# controlador_valvulas.net
KiCad netlist of a schematic drawn in EAGLE
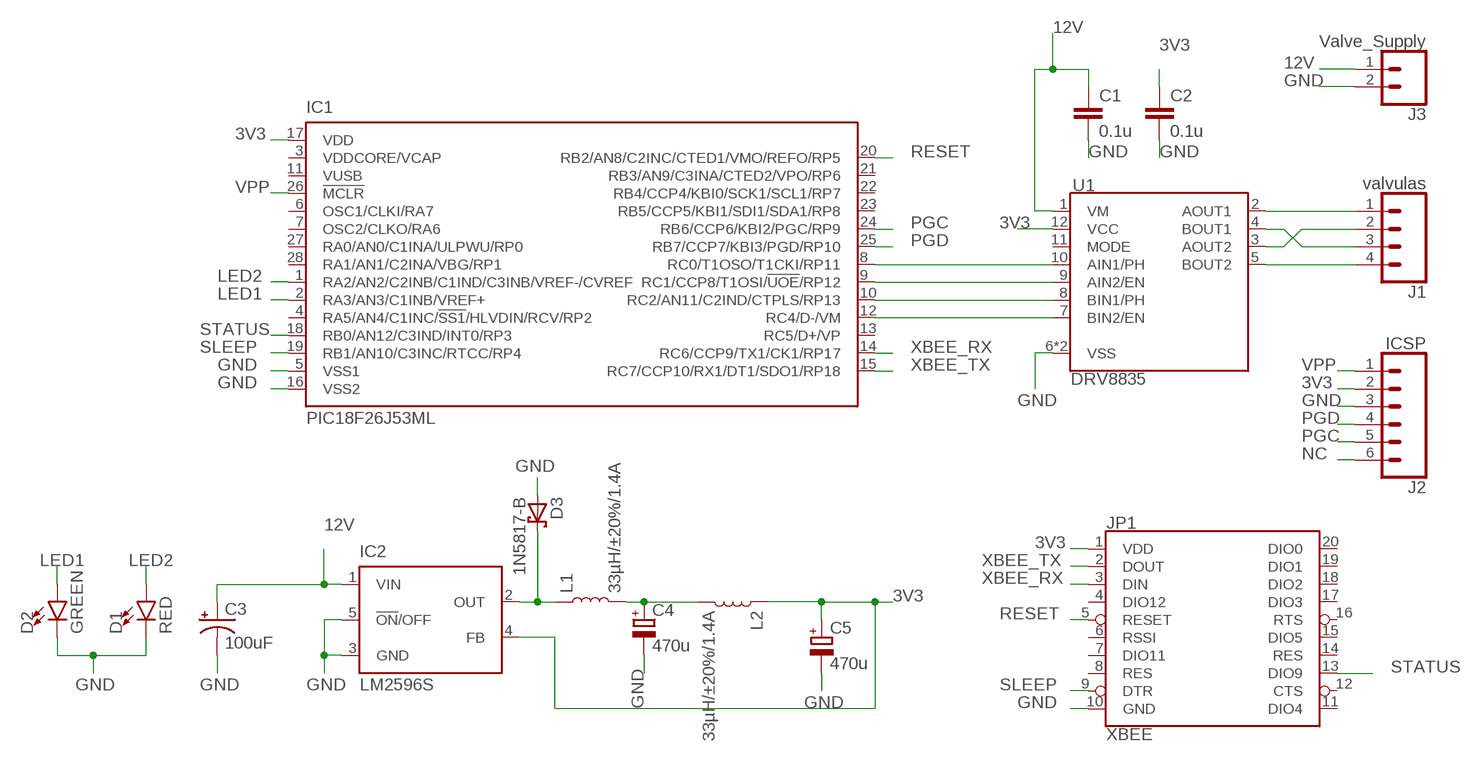
[diagram p0: schematic, sheet 1]

(export (version "E")
  (design (tool "Eeschema 10.0.6"))
  (components
    (comp (ref "C1")
      (value "0.1u")
      (footprint "eagle-import:C0805K")
      (libsource (lib "eagle-import") (part "C-EUC0805K"))
    )
    (comp (ref "C2")
      (value "0.1u")
      (footprint "eagle-import:C0805K")
      (libsource (lib "eagle-import") (part "C-EUC0805K"))
    )
    (comp (ref "C3")
      (value "100uF")
      (footprint "eagle-import:EIA7343")
      (libsource (lib "eagle-import") (part "100UF-POLAR-EIA7343-10V-10%(TANT)"))
    )
    (comp (ref "C4")
      (value "470u")
      (footprint "eagle-import:CT7343")
      (libsource (lib "eagle-import") (part "CPOL-EUCT7343"))
    )
    (comp (ref "C5")
      (value "470u")
      (footprint "eagle-import:CT7343")
      (libsource (lib "eagle-import") (part "CPOL-EUCT7343"))
    )
    (comp (ref "D1")
      (value "RED")
      (footprint "eagle-import:LED-1206")
      (libsource (lib "eagle-import") (part "LED-RED1206"))
    )
    (comp (ref "D2")
      (value "GREEN")
      (footprint "eagle-import:LED-1206")
      (libsource (lib "eagle-import") (part "LED-GREEN1206"))
    )
    (comp (ref "D3")
      (value "1N5817-B")
      (footprint "eagle-import:DO41-7.6")
      (libsource (lib "eagle-import") (part "1N5817-B"))
    )
    (comp (ref "IC1")
      (value "PIC18F26J53ML")
      (footprint "eagle-import:QFN28-ML_6X6MM")
      (fields (field (name "MPN") "PIC18F26J53-I/ML"))
      (libsource (lib "eagle-import") (part "PIC18F2J53ML6"))
    )
    (comp (ref "IC2")
      (value "LM2596S")
      (footprint "eagle-import:TO263-5")
      (fields (field (name "MF") "NATIONAL SEMICONDUCTOR") (field (name "MPN") "LM2596S-ADJ/NOPB"))
      (libsource (lib "eagle-import") (part "LM2596S"))
    )
    (comp (ref "J1")
      (value "valvulas")
      (footprint "eagle-import:1X04")
      (libsource (lib "eagle-import") (part "CONN_04"))
    )
    (comp (ref "J2")
      (value "ICSP")
      (footprint "eagle-import:1X06_LONGPADS")
      (libsource (lib "eagle-import") (part "CONN_06LONGPADS"))
    )
    (comp (ref "J3")
      (value "Valve_Supply")
      (footprint "eagle-import:1X02")
      (libsource (lib "eagle-import") (part "CONN_02"))
    )
    (comp (ref "JP1")
      (value "XBEE")
      (footprint "eagle-import:XBEE-LONGPAD")
      (libsource (lib "eagle-import") (part "XBEELONGPAD"))
    )
    (comp (ref "L1")
      (value "33µH/±20%/1.4A")
      (footprint "eagle-import:SRN6045")
      (libsource (lib "eagle-import") (part "INDUCTOR-SRN6045-33UH"))
    )
    (comp (ref "L2")
      (value "33µH/±20%/1.4A")
      (footprint "eagle-import:SRN6045")
      (libsource (lib "eagle-import") (part "INDUCTOR-SRN6045-33UH"))
    )
    (comp (ref "U1")
      (value "DRV8835")
      (footprint "eagle-import:WSON-12")
      (libsource (lib "eagle-import") (part "DRV883X"))
    )
  )
  (nets
    (net (code "1") (name "/3V3") (class "Default")
      (node (ref "C2") (pin "1") (pinfunction "1_1") (pintype "passive"))
      (node (ref "C5") (pin "+") (pinfunction "+_+") (pintype "passive"))
      (node (ref "IC1") (pin "17") (pinfunction "VDD_17") (pintype "input"))
      (node (ref "IC2") (pin "4") (pinfunction "FB_4") (pintype "input"))
      (node (ref "J2") (pin "2") (pinfunction "2_2") (pintype "passive"))
      (node (ref "JP1") (pin "1") (pinfunction "VDD_1") (pintype "power_in"))
      (node (ref "L2") (pin "1") (pinfunction "1_1") (pintype "passive"))
      (node (ref "U1") (pin "12") (pinfunction "VCC_12") (pintype "bidirectional"))
    )
    (net (code "2") (name "/12V") (class "Default")
      (node (ref "C1") (pin "1") (pinfunction "1_1") (pintype "passive"))
      (node (ref "C3") (pin "A") (pinfunction "+_A") (pintype "passive"))
      (node (ref "IC2") (pin "1") (pinfunction "VIN_1") (pintype "input"))
      (node (ref "J3") (pin "1") (pinfunction "1_1") (pintype "passive"))
      (node (ref "U1") (pin "1") (pinfunction "VM_1") (pintype "bidirectional"))
    )
    (net (code "3") (name "/GND") (class "Default")
      (node (ref "C1") (pin "2") (pinfunction "2_2") (pintype "passive"))
      (node (ref "C2") (pin "2") (pinfunction "2_2") (pintype "passive"))
      (node (ref "C3") (pin "C") (pinfunction "-_C") (pintype "passive"))
      (node (ref "C4") (pin "-") (pinfunction "-_-") (pintype "passive"))
      (node (ref "C5") (pin "-") (pinfunction "-_-") (pintype "passive"))
      (node (ref "D1") (pin "C") (pinfunction "C_C") (pintype "passive"))
      (node (ref "D2") (pin "C") (pinfunction "C_C") (pintype "passive"))
      (node (ref "D3") (pin "A") (pinfunction "A_A") (pintype "passive"))
      (node (ref "IC1") (pin "16") (pinfunction "VSS2_16") (pintype "input"))
      (node (ref "IC1") (pin "5") (pinfunction "VSS1_5") (pintype "input"))
      (node (ref "IC2") (pin "3") (pinfunction "GND_3") (pintype "power_in"))
      (node (ref "IC2") (pin "5") (pinfunction "~{ON}/OFF_5") (pintype "input"))
      (node (ref "J2") (pin "3") (pinfunction "3_3") (pintype "passive"))
      (node (ref "J3") (pin "2") (pinfunction "2_2") (pintype "passive"))
      (node (ref "JP1") (pin "10") (pinfunction "GND_10") (pintype "power_in"))
      (node (ref "U1") (pin "6") (pinfunction "VSS_6") (pintype "bidirectional"))
      (node (ref "U1") (pin "PAD") (pinfunction "VSS_PAD") (pintype "bidirectional"))
    )
    (net (code "4") (name "/LED1") (class "Default")
      (node (ref "D2") (pin "A") (pinfunction "A_A") (pintype "passive"))
      (node (ref "IC1") (pin "2") (pinfunction "RA3/AN3/C1INB/VREF+_2") (pintype "bidirectional"))
    )
    (net (code "5") (name "/LED2") (class "Default")
      (node (ref "D1") (pin "A") (pinfunction "A_A") (pintype "passive"))
      (node (ref "IC1") (pin "1") (pinfunction "RA2/AN2/C2INB/C1IND/C3INB/VREF-/CVREF_1") (pintype "bidirectional"))
    )
    (net (code "6") (name "/NC") (class "Default")
      (node (ref "J2") (pin "6") (pinfunction "6_6") (pintype "passive"))
    )
    (net (code "7") (name "/PGC") (class "Default")
      (node (ref "IC1") (pin "24") (pinfunction "RB6/CCP6/KBI2/PGC/RP9_24") (pintype "bidirectional"))
      (node (ref "J2") (pin "5") (pinfunction "5_5") (pintype "passive"))
    )
    (net (code "8") (name "/PGD") (class "Default")
      (node (ref "IC1") (pin "25") (pinfunction "RB7/CCP7/KBI3/PGD/RP10_25") (pintype "bidirectional"))
      (node (ref "J2") (pin "4") (pinfunction "4_4") (pintype "passive"))
    )
    (net (code "9") (name "/RESET") (class "Default")
      (node (ref "IC1") (pin "20") (pinfunction "RB2/AN8/C2INC/CTED1/VMO/REFO/RP5_20") (pintype "bidirectional"))
      (node (ref "JP1") (pin "5") (pinfunction "RESET_5") (pintype "input"))
    )
    (net (code "10") (name "/SLEEP") (class "Default")
      (node (ref "IC1") (pin "19") (pinfunction "RB1/AN10/C3INC/RTCC/RP4_19") (pintype "bidirectional"))
      (node (ref "JP1") (pin "9") (pinfunction "DTR_9") (pintype "bidirectional"))
    )
    (net (code "11") (name "/STATUS") (class "Default")
      (node (ref "IC1") (pin "18") (pinfunction "RB0/AN12/C3IND/INT0/RP3_18") (pintype "bidirectional"))
      (node (ref "JP1") (pin "13") (pinfunction "DIO9_13") (pintype "bidirectional"))
    )
    (net (code "12") (name "/VPP") (class "Default")
      (node (ref "IC1") (pin "26") (pinfunction "~{MCLR}_26") (pintype "input"))
      (node (ref "J2") (pin "1") (pinfunction "1_1") (pintype "passive"))
    )
    (net (code "13") (name "/XBEE_RX") (class "Default")
      (node (ref "IC1") (pin "14") (pinfunction "RC6/CCP9/TX1/CK1/RP17_14") (pintype "bidirectional"))
      (node (ref "JP1") (pin "3") (pinfunction "DIN_3") (pintype "input"))
    )
    (net (code "14") (name "/XBEE_TX") (class "Default")
      (node (ref "IC1") (pin "15") (pinfunction "RC7/CCP10/RX1/DT1/SDO1/RP18_15") (pintype "bidirectional"))
      (node (ref "JP1") (pin "2") (pinfunction "DOUT_2") (pintype "output"))
    )
    (net (code "15") (name "Net-(C4-Pad+)") (class "Default")
      (node (ref "C4") (pin "+") (pinfunction "+_+") (pintype "passive"))
      (node (ref "L1") (pin "2") (pinfunction "2_2") (pintype "passive"))
      (node (ref "L2") (pin "2") (pinfunction "2_2") (pintype "passive"))
    )
    (net (code "16") (name "Net-(IC1-RC0{slash}T1OSO{slash}T1CKI{slash}RP11)") (class "Default")
      (node (ref "IC1") (pin "8") (pinfunction "RC0/T1OSO/T1CKI/RP11_8") (pintype "bidirectional"))
      (node (ref "U1") (pin "10") (pinfunction "AIN1/PH_10") (pintype "bidirectional"))
    )
    (net (code "17") (name "Net-(IC1-RC1{slash}CCP8{slash}T1OSI{slash}~{UOE}{slash}RP12)") (class "Default")
      (node (ref "IC1") (pin "9") (pinfunction "RC1/CCP8/T1OSI/~{UOE}/RP12_9") (pintype "bidirectional"))
      (node (ref "U1") (pin "9") (pinfunction "AIN2/EN_9") (pintype "bidirectional"))
    )
    (net (code "18") (name "Net-(IC1-RC2{slash}AN11{slash}C2IND{slash}CTPLS{slash}RP13)") (class "Default")
      (node (ref "IC1") (pin "10") (pinfunction "RC2/AN11/C2IND/CTPLS/RP13_10") (pintype "bidirectional"))
      (node (ref "U1") (pin "8") (pinfunction "BIN1/PH_8") (pintype "bidirectional"))
    )
    (net (code "19") (name "Net-(IC1-RC4{slash}D-{slash}VM)") (class "Default")
      (node (ref "IC1") (pin "12") (pinfunction "RC4/D-/VM_12") (pintype "bidirectional"))
      (node (ref "U1") (pin "7") (pinfunction "BIN2/EN_7") (pintype "bidirectional"))
    )
    (net (code "20") (name "Net-(IC2-OUT)") (class "Default")
      (node (ref "D3") (pin "C") (pinfunction "C_C") (pintype "passive"))
      (node (ref "IC2") (pin "2") (pinfunction "OUT_2") (pintype "output"))
      (node (ref "L1") (pin "1") (pinfunction "1_1") (pintype "passive"))
    )
    (net (code "21") (name "Net-(U1-AOUT1)") (class "Default")
      (node (ref "J1") (pin "1") (pinfunction "1_1") (pintype "passive"))
      (node (ref "U1") (pin "2") (pinfunction "AOUT1_2") (pintype "bidirectional"))
    )
    (net (code "22") (name "Net-(U1-AOUT2)") (class "Default")
      (node (ref "J1") (pin "2") (pinfunction "2_2") (pintype "passive"))
      (node (ref "U1") (pin "3") (pinfunction "AOUT2_3") (pintype "bidirectional"))
    )
    (net (code "23") (name "Net-(U1-BOUT1)") (class "Default")
      (node (ref "J1") (pin "3") (pinfunction "3_3") (pintype "passive"))
      (node (ref "U1") (pin "4") (pinfunction "BOUT1_4") (pintype "bidirectional"))
    )
    (net (code "24") (name "Net-(U1-BOUT2)") (class "Default")
      (node (ref "J1") (pin "4") (pinfunction "4_4") (pintype "passive"))
      (node (ref "U1") (pin "5") (pinfunction "BOUT2_5") (pintype "bidirectional"))
    )
    (net (code "25") (name "unconnected-(IC1-OSC1{slash}CLKI{slash}RA7-Pad6)") (class "Default")
      (node (ref "IC1") (pin "6") (pinfunction "OSC1/CLKI/RA7_6") (pintype "bidirectional"))
    )
    (net (code "26") (name "unconnected-(IC1-OSC2{slash}CLKO{slash}RA6-Pad7)") (class "Default")
      (node (ref "IC1") (pin "7") (pinfunction "OSC2/CLKO/RA6_7") (pintype "bidirectional"))
    )
    (net (code "27") (name "unconnected-(IC1-RA0{slash}AN0{slash}C1INA{slash}ULPWU{slash}RP0-Pad27)") (class "Default")
      (node (ref "IC1") (pin "27") (pinfunction "RA0/AN0/C1INA/ULPWU/RP0_27") (pintype "bidirectional"))
    )
    (net (code "28") (name "unconnected-(IC1-RA1{slash}AN1{slash}C2INA{slash}VBG{slash}RP1-Pad28)") (class "Default")
      (node (ref "IC1") (pin "28") (pinfunction "RA1/AN1/C2INA/VBG/RP1_28") (pintype "bidirectional"))
    )
    (net (code "29") (name "unconnected-(IC1-RA5{slash}AN4{slash}C1INC{slash}~{SS1}{slash}HLVDIN{slash}RCV{slash}RP2-Pad4)") (class "Default")
      (node (ref "IC1") (pin "4") (pinfunction "RA5/AN4/C1INC/~{SS1}/HLVDIN/RCV/RP2_4") (pintype "bidirectional"))
    )
    (net (code "30") (name "unconnected-(IC1-RB3{slash}AN9{slash}C3INA{slash}CTED2{slash}VPO{slash}RP6-Pad21)") (class "Default")
      (node (ref "IC1") (pin "21") (pinfunction "RB3/AN9/C3INA/CTED2/VPO/RP6_21") (pintype "bidirectional"))
    )
    (net (code "31") (name "unconnected-(IC1-RB4{slash}CCP4{slash}KBI0{slash}SCK1{slash}SCL1{slash}RP7-Pad22)") (class "Default")
      (node (ref "IC1") (pin "22") (pinfunction "RB4/CCP4/KBI0/SCK1/SCL1/RP7_22") (pintype "bidirectional"))
    )
    (net (code "32") (name "unconnected-(IC1-RB5{slash}CCP5{slash}KBI1{slash}SDI1{slash}SDA1{slash}RP8-Pad23)") (class "Default")
      (node (ref "IC1") (pin "23") (pinfunction "RB5/CCP5/KBI1/SDI1/SDA1/RP8_23") (pintype "bidirectional"))
    )
    (net (code "33") (name "unconnected-(IC1-RC5{slash}D+{slash}VP-Pad13)") (class "Default")
      (node (ref "IC1") (pin "13") (pinfunction "RC5/D+/VP_13") (pintype "bidirectional"))
    )
    (net (code "34") (name "unconnected-(IC1-VDDCORE{slash}VCAP-Pad3)") (class "Default")
      (node (ref "IC1") (pin "3") (pinfunction "VDDCORE/VCAP_3") (pintype "input"))
    )
    (net (code "35") (name "unconnected-(IC1-VUSB-Pad11)") (class "Default")
      (node (ref "IC1") (pin "11") (pinfunction "VUSB_11") (pintype "input"))
    )
    (net (code "36") (name "unconnected-(JP1-CTS-Pad12)") (class "Default")
      (node (ref "JP1") (pin "12") (pinfunction "CTS_12") (pintype "output"))
    )
    (net (code "37") (name "unconnected-(JP1-DIO0-Pad20)") (class "Default")
      (node (ref "JP1") (pin "20") (pinfunction "DIO0_20") (pintype "bidirectional"))
    )
    (net (code "38") (name "unconnected-(JP1-DIO1-Pad19)") (class "Default")
      (node (ref "JP1") (pin "19") (pinfunction "DIO1_19") (pintype "bidirectional"))
    )
    (net (code "39") (name "unconnected-(JP1-DIO2-Pad18)") (class "Default")
      (node (ref "JP1") (pin "18") (pinfunction "DIO2_18") (pintype "bidirectional"))
    )
    (net (code "40") (name "unconnected-(JP1-DIO3-Pad17)") (class "Default")
      (node (ref "JP1") (pin "17") (pinfunction "DIO3_17") (pintype "bidirectional"))
    )
    (net (code "41") (name "unconnected-(JP1-DIO4-Pad11)") (class "Default")
      (node (ref "JP1") (pin "11") (pinfunction "DIO4_11") (pintype "bidirectional"))
    )
    (net (code "42") (name "unconnected-(JP1-DIO5-Pad15)") (class "Default")
      (node (ref "JP1") (pin "15") (pinfunction "DIO5_15") (pintype "bidirectional"))
    )
    (net (code "43") (name "unconnected-(JP1-DIO11-Pad7)") (class "Default")
      (node (ref "JP1") (pin "7") (pinfunction "DIO11_7") (pintype "bidirectional"))
    )
    (net (code "44") (name "unconnected-(JP1-DIO12-Pad4)") (class "Default")
      (node (ref "JP1") (pin "4") (pinfunction "DIO12_4") (pintype "bidirectional"))
    )
    (net (code "45") (name "unconnected-(JP1-RES-Pad8)") (class "Default")
      (node (ref "JP1") (pin "8") (pinfunction "RES_8") (pintype "bidirectional"))
    )
    (net (code "46") (name "unconnected-(JP1-RES-Pad14)") (class "Default")
      (node (ref "JP1") (pin "14") (pinfunction "RES_14") (pintype "bidirectional"))
    )
    (net (code "47") (name "unconnected-(JP1-RSSI-Pad6)") (class "Default")
      (node (ref "JP1") (pin "6") (pinfunction "RSSI_6") (pintype "bidirectional"))
    )
    (net (code "48") (name "unconnected-(JP1-RTS-Pad16)") (class "Default")
      (node (ref "JP1") (pin "16") (pinfunction "RTS_16") (pintype "input"))
    )
    (net (code "49") (name "unconnected-(U1-MODE-Pad11)") (class "Default")
      (node (ref "U1") (pin "11") (pinfunction "MODE_11") (pintype "bidirectional"))
    )
  )
)
